# ProPrj_1300__2024-07-27.net
KiCad netlist of a schematic drawn in EasyEDA Pro
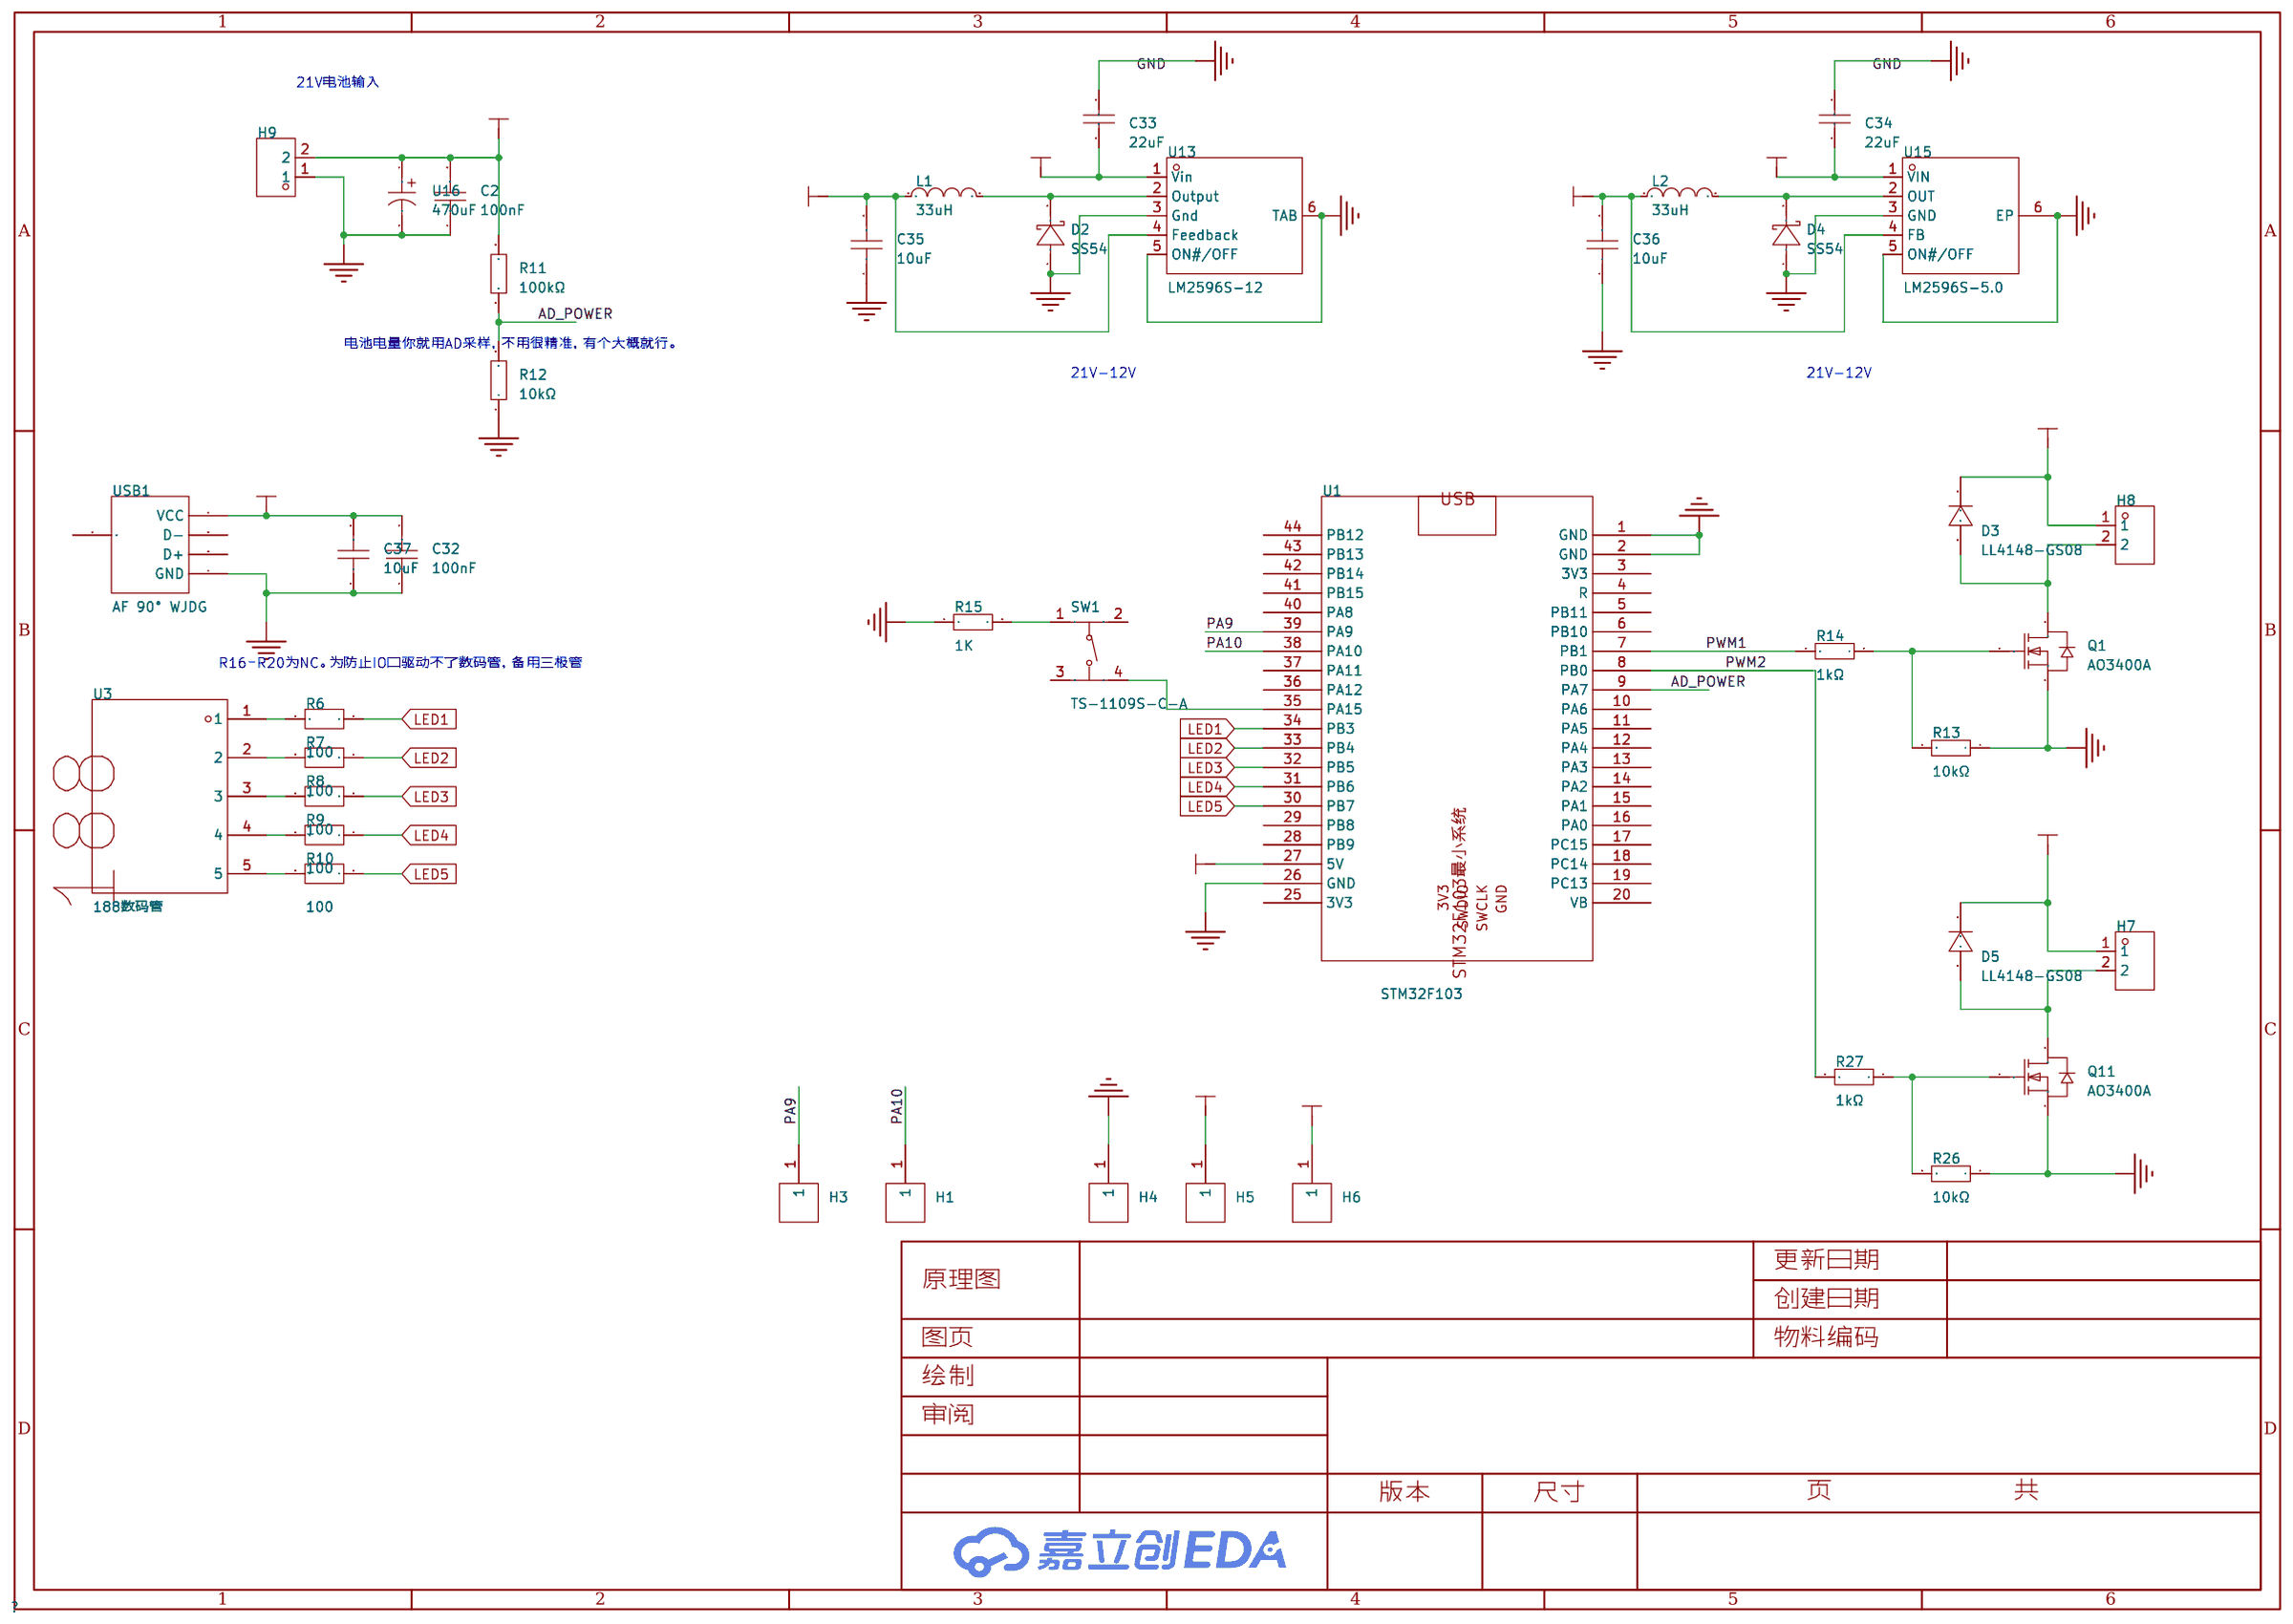
[diagram p0: schematic sheet]

(export (version "E")
  (design (tool "Eeschema 10.0.6"))
  (components
    (comp (ref "C2")
      (value "100nF")
      (footprint "easyedapro:C0603")
      (description "容值:100nF;精度:±10%;额定电压:50V;材质(温度系数):X7R;")
      (fields
        (field (name "Manufacturer Part") "CC0603KRX7R9BB104")
        (field (name "Manufacturer") "YAGEO(国巨)")
      )
      (libsource (lib "easyedapro") (part "CC0603KRX7R9BB104"))
    )
    (comp (ref "C32")
      (value "100nF")
      (footprint "easyedapro:C0603")
      (description "容值:100nF;精度:±10%;额定电压:50V;材质(温度系数):X7R;")
      (fields
        (field (name "Manufacturer Part") "CC0603KRX7R9BB104")
        (field (name "Manufacturer") "YAGEO(国巨)")
      )
      (libsource (lib "easyedapro") (part "CC0603KRX7R9BB104"))
    )
    (comp (ref "C33")
      (value "22uF")
      (footprint "easyedapro:C1206")
      (description "容值:22uF;精度:±10%;额定电压:25V;材质(温度系数):X5R;")
      (fields
        (field (name "Manufacturer Part") "CL31A226KAHNNNE")
        (field (name "Manufacturer") "SAMSUNG(三星)")
      )
      (libsource (lib "easyedapro") (part "CL31A226KAHNNNE"))
    )
    (comp (ref "C34")
      (value "22uF")
      (footprint "easyedapro:C1206")
      (description "容值:22uF;精度:±10%;额定电压:25V;材质(温度系数):X5R;")
      (fields
        (field (name "Manufacturer Part") "CL31A226KAHNNNE")
        (field (name "Manufacturer") "SAMSUNG(三星)")
      )
      (libsource (lib "easyedapro") (part "CL31A226KAHNNNE"))
    )
    (comp (ref "C35")
      (value "10uF")
      (footprint "easyedapro:C0805")
      (description "容值:10uF;精度:±10%;额定电压:25V;材质(温度系数):X5R;")
      (fields
        (field (name "Manufacturer Part") "CL21A106KAYNNNE")
        (field (name "Manufacturer") "SAMSUNG(三星)")
      )
      (libsource (lib "easyedapro") (part "CL21A106KAYNNNE"))
    )
    (comp (ref "C36")
      (value "10uF")
      (footprint "easyedapro:C0805")
      (description "容值:10uF;精度:±10%;额定电压:25V;材质(温度系数):X5R;")
      (fields
        (field (name "Manufacturer Part") "CL21A106KAYNNNE")
        (field (name "Manufacturer") "SAMSUNG(三星)")
      )
      (libsource (lib "easyedapro") (part "CL21A106KAYNNNE"))
    )
    (comp (ref "C37")
      (value "10uF")
      (footprint "easyedapro:C0805")
      (description "容值:10uF;精度:±10%;额定电压:25V;材质(温度系数):X5R;")
      (fields
        (field (name "Manufacturer Part") "CL21A106KAYNNNE")
        (field (name "Manufacturer") "SAMSUNG(三星)")
      )
      (libsource (lib "easyedapro") (part "CL21A106KAYNNNE"))
    )
    (comp (ref "D2")
      (value "SS54")
      (footprint "easyedapro:SMA_L4.3-W2.6-LS5.0-FD")
      (description "二极管配置:独立式;正向压降(Vf):550mV@5.0A;直流反向耐压(Vr):40V;平均整流电流(Io):5A;")
      (fields (field (name "Manufacturer") "宏迦橙"))
      (libsource (lib "easyedapro") (part "SS54_C7420369"))
    )
    (comp (ref "D3")
      (value "LL4148-GS08")
      (footprint "easyedapro:SOD-80_L3.5-W1.5-RD")
      (description "二极管配置:-;正向压降(Vf):860mV@50mA;直流反向耐压(Vr):75V;平均整流电流(Io):300mA;功率:500mW;反向恢复时间(trr):8ns;")
      (fields (field (name "Manufacturer") "VISHAY(威世)"))
      (libsource (lib "easyedapro") (part "LL4148-GS08"))
    )
    (comp (ref "D4")
      (value "SS54")
      (footprint "easyedapro:SMA_L4.3-W2.6-LS5.0-FD")
      (description "二极管配置:独立式;正向压降(Vf):550mV@5.0A;直流反向耐压(Vr):40V;平均整流电流(Io):5A;")
      (fields (field (name "Manufacturer") "宏迦橙"))
      (libsource (lib "easyedapro") (part "SS54_C7420369"))
    )
    (comp (ref "D5")
      (value "LL4148-GS08")
      (footprint "easyedapro:SOD-80_L3.5-W1.5-RD")
      (description "二极管配置:-;正向压降(Vf):860mV@50mA;直流反向耐压(Vr):75V;平均整流电流(Io):300mA;功率:500mW;反向恢复时间(trr):8ns;")
      (fields (field (name "Manufacturer") "VISHAY(威世)"))
      (libsource (lib "easyedapro") (part "LL4148-GS08"))
    )
    (comp (ref "H1")
      (value "PZ254V-11-01P")
      (footprint "easyedapro:HDR-TH_1P-P2.54-V-M")
      (fields (field (name "Manufacturer") "XFCN(兴飞)"))
      (libsource (lib "easyedapro") (part "PZ254V-11-01P"))
    )
    (comp (ref "H3")
      (value "PZ254V-11-01P")
      (footprint "easyedapro:HDR-TH_1P-P2.54-V-M")
      (fields (field (name "Manufacturer") "XFCN(兴飞)"))
      (libsource (lib "easyedapro") (part "PZ254V-11-01P"))
    )
    (comp (ref "H4")
      (value "PZ254V-11-01P")
      (footprint "easyedapro:HDR-TH_1P-P2.54-V-M")
      (fields (field (name "Manufacturer") "XFCN(兴飞)"))
      (libsource (lib "easyedapro") (part "PZ254V-11-01P"))
    )
    (comp (ref "H5")
      (value "PZ254V-11-01P")
      (footprint "easyedapro:HDR-TH_1P-P2.54-V-M")
      (fields (field (name "Manufacturer") "XFCN(兴飞)"))
      (libsource (lib "easyedapro") (part "PZ254V-11-01P"))
    )
    (comp (ref "H6")
      (value "PZ254V-11-01P")
      (footprint "easyedapro:HDR-TH_1P-P2.54-V-M")
      (fields (field (name "Manufacturer") "XFCN(兴飞)"))
      (libsource (lib "easyedapro") (part "PZ254V-11-01P"))
    )
    (comp (ref "H7")
      (value "PZ254V-11-02P")
      (footprint "easyedapro:HDR-TH_2P-P2.54-V-M")
      (fields (field (name "Manufacturer") "XFCN(兴飞)"))
      (libsource (lib "easyedapro") (part "PZ254V-11-02P"))
    )
    (comp (ref "H8")
      (value "PZ254V-11-02P")
      (footprint "easyedapro:HDR-TH_2P-P2.54-V-M")
      (fields (field (name "Manufacturer") "XFCN(兴飞)"))
      (libsource (lib "easyedapro") (part "PZ254V-11-02P"))
    )
    (comp (ref "H9")
      (value "PZ254V-11-02P")
      (footprint "easyedapro:HDR-TH_2P-P2.54-V-M")
      (fields (field (name "Manufacturer") "XFCN(兴飞)"))
      (libsource (lib "easyedapro") (part "PZ254V-11-02P"))
    )
    (comp (ref "L1")
      (value "33uH")
      (footprint "easyedapro:IND-SMD_L7.0-W6.6_FXL0630")
      (description "电感值:33uH;精度:±20%;额定电流:2A;饱和电流(Isat):2.5A;类型:一体成型电感;")
      (fields (field (name "Manufacturer Part") "FXL0630-330-M") (field (name "Manufacturer") "cjiang(长江微电)"))
      (libsource (lib "easyedapro") (part "FXL0630-330-M"))
    )
    (comp (ref "L2")
      (value "33uH")
      (footprint "easyedapro:IND-SMD_L7.0-W6.6_FXL0630")
      (description "电感值:33uH;精度:±20%;额定电流:2A;饱和电流(Isat):2.5A;类型:一体成型电感;")
      (fields (field (name "Manufacturer Part") "FXL0630-330-M") (field (name "Manufacturer") "cjiang(长江微电)"))
      (libsource (lib "easyedapro") (part "FXL0630-330-M"))
    )
    (comp (ref "Q1")
      (value "AO3400A")
      (footprint "easyedapro:SOT-23-3_L2.9-W1.6-P1.90-LS2.8-BR")
      (fields (field (name "Manufacturer") "AOS"))
      (libsource (lib "easyedapro") (part "AO3400A"))
    )
    (comp (ref "Q11")
      (value "AO3400A")
      (footprint "easyedapro:SOT-23-3_L2.9-W1.6-P1.90-LS2.8-BR")
      (fields (field (name "Manufacturer") "AOS"))
      (libsource (lib "easyedapro") (part "AO3400A"))
    )
    (comp (ref "R6") (value "100") (footprint "easyedapro:R0603") (libsource (lib "easyedapro") (part "100")))
    (comp (ref "R7") (value "100") (footprint "easyedapro:R0603") (libsource (lib "easyedapro") (part "100")))
    (comp (ref "R8") (value "100") (footprint "easyedapro:R0603") (libsource (lib "easyedapro") (part "100")))
    (comp (ref "R9") (value "100") (footprint "easyedapro:R0603") (libsource (lib "easyedapro") (part "100")))
    (comp (ref "R10")
      (value "100")
      (footprint "easyedapro:R0603")
      (libsource (lib "easyedapro") (part "100"))
    )
    (comp (ref "R11")
      (value "100kΩ")
      (footprint "easyedapro:R0603")
      (description "电阻类型:厚膜电阻;阻值:100kΩ;精度:±1%;功率:100mW;最大工作电压:75V;温度系数:±100ppm/°C;")
      (fields (field (name "Manufacturer Part") "RC0603FR-07100KL") (field (name "Manufacturer") "YAGEO(国巨)"))
      (libsource (lib "easyedapro") (part "RC0603FR-07100KL"))
    )
    (comp (ref "R12")
      (value "10kΩ")
      (footprint "easyedapro:R0603")
      (description "电阻类型:厚膜电阻;阻值:10kΩ;精度:±1%;功率:100mW;最大工作电压:75V;温度系数:±100ppm/°C;")
      (fields
        (field (name "Manufacturer Part") "0603WAF1002T5E")
        (field (name "Manufacturer") "UNI-ROYAL(厚声)")
      )
      (libsource (lib "easyedapro") (part "0603WAF1002T5E"))
    )
    (comp (ref "R13")
      (value "10kΩ")
      (footprint "easyedapro:R0603")
      (description "电阻类型:厚膜电阻;阻值:10kΩ;精度:±1%;功率:100mW;最大工作电压:75V;温度系数:±100ppm/°C;")
      (fields
        (field (name "Manufacturer Part") "0603WAF1002T5E")
        (field (name "Manufacturer") "UNI-ROYAL(厚声)")
      )
      (libsource (lib "easyedapro") (part "0603WAF1002T5E"))
    )
    (comp (ref "R14")
      (value "1kΩ")
      (footprint "easyedapro:R0603")
      (description "电阻类型:厚膜电阻;阻值:1kΩ;精度:±1%;功率:100mW;最大工作电压:75V;温度系数:±100ppm/°C;")
      (fields
        (field (name "Manufacturer Part") "0603WAF1001T5E")
        (field (name "Manufacturer") "UNI-ROYAL(厚声)")
      )
      (libsource (lib "easyedapro") (part "0603WAF1001T5E"))
    )
    (comp (ref "R15")
      (value "1K")
      (footprint "easyedapro:R0603")
      (description "电阻类型:厚膜电阻;阻值:10kΩ;精度:±1%;功率:100mW;最大工作电压:75V;温度系数:±100ppm/°C;")
      (fields
        (field (name "Manufacturer Part") "0603WAF1002T5E")
        (field (name "Manufacturer") "UNI-ROYAL(厚声)")
      )
      (libsource (lib "easyedapro") (part "0603WAF1002T5E"))
    )
    (comp (ref "R26")
      (value "10kΩ")
      (footprint "easyedapro:R0603")
      (description "电阻类型:厚膜电阻;阻值:10kΩ;精度:±1%;功率:100mW;最大工作电压:75V;温度系数:±100ppm/°C;")
      (fields
        (field (name "Manufacturer Part") "0603WAF1002T5E")
        (field (name "Manufacturer") "UNI-ROYAL(厚声)")
      )
      (libsource (lib "easyedapro") (part "0603WAF1002T5E"))
    )
    (comp (ref "R27")
      (value "1kΩ")
      (footprint "easyedapro:R0603")
      (description "电阻类型:厚膜电阻;阻值:1kΩ;精度:±1%;功率:100mW;最大工作电压:75V;温度系数:±100ppm/°C;")
      (fields
        (field (name "Manufacturer Part") "0603WAF1001T5E")
        (field (name "Manufacturer") "UNI-ROYAL(厚声)")
      )
      (libsource (lib "easyedapro") (part "0603WAF1001T5E"))
    )
    (comp (ref "SW1")
      (value "TS-1109S-C-A")
      (footprint "easyedapro:SW-SMD_4P-L4.5-W4.5-P3.00-LS7.0")
      (fields (field (name "Manufacturer") "XKB Connectivity(中国星坤)"))
      (libsource (lib "easyedapro") (part "TS-1109S-C-A"))
    )
    (comp (ref "U1")
      (value "STM32F103")
      (footprint "easyedapro:STM32FF103")
      (libsource (lib "easyedapro") (part "STM32F103"))
    )
    (comp (ref "U3") (value "188数码管") (libsource (lib "easyedapro") (part "188数码管")))
    (comp (ref "U13")
      (value "LM2596S-12")
      (footprint "easyedapro:TO-263-5_L10.0-W8.4-P1.70-LS15.3-BR")
      (description "功能类型:降压型;输出类型:固定;输入电压:40V;输出电压:12V;输出电流(最大值):3A;")
      (fields (field (name "Manufacturer") "UMW(友台半导体)"))
      (libsource (lib "easyedapro") (part "LM2596S-12"))
    )
    (comp (ref "U15")
      (value "LM2596S-5.0")
      (footprint "easyedapro:TO-263-5_L10.2-W8.9-P1.70-BR")
      (description "功能类型:降压型;输出类型:固定;输入电压:40V;输出电压:5V;输出电流(最大值):3A;")
      (fields (field (name "Manufacturer") "UMW(友台半导体)"))
      (libsource (lib "easyedapro") (part "LM2596S-5.0"))
    )
    (comp (ref "U16")
      (value "470uF")
      (footprint "easyedapro:CAP-TH_BD6.3-P2.50-D0.6-FD")
      (description "容值:470uF;精度:±20%;额定电压:25V;纹波电流:2.05A;等效串联电阻:35mΩ;")
      (fields (field (name "Manufacturer Part") "HT1E477M0611PC") (field (name "Manufacturer") "HONOR(荣誉)"))
      (libsource (lib "easyedapro") (part "HT1E477M0611PC"))
    )
    (comp (ref "USB1")
      (value "AF 90° WJDG")
      (footprint "easyedapro:USB-A-TH_AF-WJDG")
      (description "连接器类型:Type-A;标准:USB 2.0;公母:母;端口数量:1;触点数量:4P;安装方式:弯插;额定电流 - 电源:1.5A;工作温度范围:-25°C~+85°C;")
      (fields (field (name "Manufacturer") "SHOU HAN(首韩)"))
      (libsource (lib "easyedapro") (part "AF 90° WJDG"))
    )
  )
  (nets
    (net (code "1") (name "+5V") (class "Default")
      (node (ref "C32") (pin "2") (pinfunction "2_2") (pintype "unspecified"))
      (node (ref "C36") (pin "2") (pinfunction "2_2") (pintype "unspecified"))
      (node (ref "C37") (pin "2") (pinfunction "2_2") (pintype "unspecified"))
      (node (ref "H5") (pin "1") (pinfunction "1_1") (pintype "unspecified"))
      (node (ref "L2") (pin "1") (pinfunction "1_1") (pintype "unspecified"))
      (node (ref "U1") (pin "27") (pinfunction "5V_27") (pintype "unspecified"))
      (node (ref "U15") (pin "4") (pinfunction "FB_4") (pintype "unspecified"))
      (node (ref "USB1") (pin "1") (pinfunction "VCC_1") (pintype "input"))
    )
    (net (code "2") (name "/AD_POWER") (class "Default")
      (node (ref "R11") (pin "1") (pinfunction "1_1") (pintype "unspecified"))
      (node (ref "R12") (pin "2") (pinfunction "2_2") (pintype "input"))
      (node (ref "U1") (pin "9") (pinfunction "PA7_9") (pintype "unspecified"))
    )
    (net (code "3") (name "/PA9") (class "Default")
      (node (ref "H3") (pin "1") (pinfunction "1_1") (pintype "unspecified"))
      (node (ref "U1") (pin "39") (pinfunction "PA9_39") (pintype "unspecified"))
    )
    (net (code "4") (name "/PA10") (class "Default")
      (node (ref "H1") (pin "1") (pinfunction "1_1") (pintype "unspecified"))
      (node (ref "U1") (pin "38") (pinfunction "PA10_38") (pintype "unspecified"))
    )
    (net (code "5") (name "/PWM1") (class "Default")
      (node (ref "R14") (pin "2") (pinfunction "2_2") (pintype "input"))
      (node (ref "U1") (pin "7") (pinfunction "PB1_7") (pintype "unspecified"))
    )
    (net (code "6") (name "/PWM2") (class "Default")
      (node (ref "R27") (pin "2") (pinfunction "2_2") (pintype "input"))
      (node (ref "U1") (pin "8") (pinfunction "PB0_8") (pintype "unspecified"))
    )
    (net (code "7") (name "12V") (class "Default")
      (node (ref "C34") (pin "1") (pinfunction "1_1") (pintype "input"))
      (node (ref "C35") (pin "2") (pinfunction "2_2") (pintype "unspecified"))
      (node (ref "D3") (pin "1") (pinfunction "C_1") (pintype "unspecified"))
      (node (ref "D5") (pin "1") (pinfunction "C_1") (pintype "unspecified"))
      (node (ref "H6") (pin "1") (pinfunction "1_1") (pintype "unspecified"))
      (node (ref "H7") (pin "1") (pinfunction "1_1") (pintype "unspecified"))
      (node (ref "H8") (pin "1") (pinfunction "1_1") (pintype "unspecified"))
      (node (ref "L1") (pin "1") (pinfunction "1_1") (pintype "unspecified"))
      (node (ref "U13") (pin "4") (pinfunction "Feedback_4") (pintype "unspecified"))
      (node (ref "U15") (pin "1") (pinfunction "VIN_1") (pintype "unspecified"))
    )
    (net (code "8") (name "21V") (class "Default")
      (node (ref "C2") (pin "2") (pinfunction "2_2") (pintype "unspecified"))
      (node (ref "C33") (pin "1") (pinfunction "1_1") (pintype "input"))
      (node (ref "H9") (pin "2") (pinfunction "2_2") (pintype "unspecified"))
      (node (ref "R11") (pin "2") (pinfunction "2_2") (pintype "unspecified"))
      (node (ref "U13") (pin "1") (pinfunction "Vin_1") (pintype "unspecified"))
      (node (ref "U16") (pin "1") (pinfunction "1_1") (pintype "input"))
    )
    (net (code "9") (name "GND") (class "Default")
      (node (ref "C2") (pin "1") (pinfunction "1_1") (pintype "unspecified"))
      (node (ref "C32") (pin "1") (pinfunction "1_1") (pintype "unspecified"))
      (node (ref "C33") (pin "2") (pinfunction "2_2") (pintype "input"))
      (node (ref "C34") (pin "2") (pinfunction "2_2") (pintype "input"))
      (node (ref "C35") (pin "1") (pinfunction "1_1") (pintype "unspecified"))
      (node (ref "C36") (pin "1") (pinfunction "1_1") (pintype "unspecified"))
      (node (ref "C37") (pin "1") (pinfunction "1_1") (pintype "unspecified"))
      (node (ref "D2") (pin "1") (pinfunction "A_1") (pintype "unspecified"))
      (node (ref "D4") (pin "1") (pinfunction "A_1") (pintype "unspecified"))
      (node (ref "H4") (pin "1") (pinfunction "1_1") (pintype "unspecified"))
      (node (ref "H9") (pin "1") (pinfunction "1_1") (pintype "unspecified"))
      (node (ref "Q1") (pin "2") (pinfunction "S_2") (pintype "unspecified"))
      (node (ref "Q11") (pin "2") (pinfunction "S_2") (pintype "unspecified"))
      (node (ref "R12") (pin "1") (pinfunction "1_1") (pintype "input"))
      (node (ref "R13") (pin "1") (pinfunction "1_1") (pintype "input"))
      (node (ref "R15") (pin "1") (pinfunction "1_1") (pintype "input"))
      (node (ref "R26") (pin "1") (pinfunction "1_1") (pintype "input"))
      (node (ref "U1") (pin "1") (pinfunction "GND_1") (pintype "unspecified"))
      (node (ref "U1") (pin "2") (pinfunction "GND_2") (pintype "unspecified"))
      (node (ref "U1") (pin "26") (pinfunction "GND_26") (pintype "unspecified"))
      (node (ref "U13") (pin "3") (pinfunction "Gnd_3") (pintype "unspecified"))
      (node (ref "U13") (pin "5") (pinfunction "ON#/OFF_5") (pintype "unspecified"))
      (node (ref "U13") (pin "6") (pinfunction "TAB_6") (pintype "unspecified"))
      (node (ref "U15") (pin "3") (pinfunction "GND_3") (pintype "unspecified"))
      (node (ref "U15") (pin "5") (pinfunction "ON#/OFF_5") (pintype "unspecified"))
      (node (ref "U15") (pin "6") (pinfunction "EP_6") (pintype "unspecified"))
      (node (ref "U16") (pin "2") (pinfunction "2_2") (pintype "input"))
      (node (ref "USB1") (pin "4") (pinfunction "GND_4") (pintype "input"))
    )
    (net (code "10") (name "LED1") (class "Default")
      (node (ref "R6") (pin "1") (pinfunction "1_1") (pintype "unspecified"))
      (node (ref "U1") (pin "34") (pinfunction "PB3_34") (pintype "unspecified"))
    )
    (net (code "11") (name "LED2") (class "Default")
      (node (ref "R7") (pin "1") (pinfunction "1_1") (pintype "unspecified"))
      (node (ref "U1") (pin "33") (pinfunction "PB4_33") (pintype "unspecified"))
    )
    (net (code "12") (name "LED3") (class "Default")
      (node (ref "R8") (pin "1") (pinfunction "1_1") (pintype "unspecified"))
      (node (ref "U1") (pin "32") (pinfunction "PB5_32") (pintype "unspecified"))
    )
    (net (code "13") (name "LED4") (class "Default")
      (node (ref "R9") (pin "1") (pinfunction "1_1") (pintype "unspecified"))
      (node (ref "U1") (pin "31") (pinfunction "PB6_31") (pintype "unspecified"))
    )
    (net (code "14") (name "LED5") (class "Default")
      (node (ref "R10") (pin "1") (pinfunction "1_1") (pintype "unspecified"))
      (node (ref "U1") (pin "30") (pinfunction "PB7_30") (pintype "unspecified"))
    )
    (net (code "15") (name "Net-(D2-K)") (class "Default")
      (node (ref "D2") (pin "2") (pinfunction "K_2") (pintype "unspecified"))
      (node (ref "L1") (pin "2") (pinfunction "2_2") (pintype "unspecified"))
      (node (ref "U13") (pin "2") (pinfunction "Output_2") (pintype "unspecified"))
    )
    (net (code "16") (name "Net-(D3-A)") (class "Default")
      (node (ref "D3") (pin "2") (pinfunction "A_2") (pintype "unspecified"))
      (node (ref "H8") (pin "2") (pinfunction "2_2") (pintype "unspecified"))
      (node (ref "Q1") (pin "3") (pinfunction "D_3") (pintype "unspecified"))
    )
    (net (code "17") (name "Net-(D4-K)") (class "Default")
      (node (ref "D4") (pin "2") (pinfunction "K_2") (pintype "unspecified"))
      (node (ref "L2") (pin "2") (pinfunction "2_2") (pintype "unspecified"))
      (node (ref "U15") (pin "2") (pinfunction "OUT_2") (pintype "unspecified"))
    )
    (net (code "18") (name "Net-(D5-A)") (class "Default")
      (node (ref "D5") (pin "2") (pinfunction "A_2") (pintype "unspecified"))
      (node (ref "H7") (pin "2") (pinfunction "2_2") (pintype "unspecified"))
      (node (ref "Q11") (pin "3") (pinfunction "D_3") (pintype "unspecified"))
    )
    (net (code "19") (name "Net-(Q1-G)") (class "Default")
      (node (ref "Q1") (pin "1") (pinfunction "G_1") (pintype "unspecified"))
      (node (ref "R13") (pin "2") (pinfunction "2_2") (pintype "input"))
      (node (ref "R14") (pin "1") (pinfunction "1_1") (pintype "input"))
    )
    (net (code "20") (name "Net-(Q11-G)") (class "Default")
      (node (ref "Q11") (pin "1") (pinfunction "G_1") (pintype "unspecified"))
      (node (ref "R26") (pin "2") (pinfunction "2_2") (pintype "input"))
      (node (ref "R27") (pin "1") (pinfunction "1_1") (pintype "input"))
    )
    (net (code "21") (name "Net-(R6-Pad2)") (class "Default")
      (node (ref "R6") (pin "2") (pinfunction "2_2") (pintype "unspecified"))
      (node (ref "U3") (pin "1") (pinfunction "1_1") (pintype "unspecified"))
    )
    (net (code "22") (name "Net-(R7-Pad2)") (class "Default")
      (node (ref "R7") (pin "2") (pinfunction "2_2") (pintype "unspecified"))
      (node (ref "U3") (pin "2") (pinfunction "2_2") (pintype "unspecified"))
    )
    (net (code "23") (name "Net-(R8-Pad2)") (class "Default")
      (node (ref "R8") (pin "2") (pinfunction "2_2") (pintype "unspecified"))
      (node (ref "U3") (pin "3") (pinfunction "3_3") (pintype "unspecified"))
    )
    (net (code "24") (name "Net-(R9-Pad2)") (class "Default")
      (node (ref "R9") (pin "2") (pinfunction "2_2") (pintype "unspecified"))
      (node (ref "U3") (pin "4") (pinfunction "4_4") (pintype "unspecified"))
    )
    (net (code "25") (name "Net-(R10-Pad2)") (class "Default")
      (node (ref "R10") (pin "2") (pinfunction "2_2") (pintype "unspecified"))
      (node (ref "U3") (pin "5") (pinfunction "5_5") (pintype "unspecified"))
    )
    (net (code "26") (name "Net-(R15-Pad2)") (class "Default")
      (node (ref "R15") (pin "2") (pinfunction "2_2") (pintype "input"))
      (node (ref "SW1") (pin "1") (pinfunction "1_1") (pintype "unspecified"))
    )
    (net (code "27") (name "Net-(U1-PA15)") (class "Default")
      (node (ref "SW1") (pin "4") (pinfunction "4_4") (pintype "unspecified"))
      (node (ref "U1") (pin "35") (pinfunction "PA15_35") (pintype "unspecified"))
    )
    (net (code "28") (name "unconnected-(SW1-Pad2)") (class "Default")
      (node (ref "SW1") (pin "2") (pinfunction "2_2") (pintype "unspecified"))
    )
    (net (code "29") (name "unconnected-(SW1-Pad3)") (class "Default")
      (node (ref "SW1") (pin "3") (pinfunction "3_3") (pintype "unspecified"))
    )
    (net (code "30") (name "unconnected-(U1-3V3-Pad3)") (class "Default")
      (node (ref "U1") (pin "3") (pinfunction "3V3_3") (pintype "unspecified"))
    )
    (net (code "31") (name "unconnected-(U1-3V3-Pad25)") (class "Default")
      (node (ref "U1") (pin "25") (pinfunction "3V3_25") (pintype "unspecified"))
    )
    (net (code "32") (name "unconnected-(U1-PA0-Pad16)") (class "Default")
      (node (ref "U1") (pin "16") (pinfunction "PA0_16") (pintype "unspecified"))
    )
    (net (code "33") (name "unconnected-(U1-PA1-Pad15)") (class "Default")
      (node (ref "U1") (pin "15") (pinfunction "PA1_15") (pintype "unspecified"))
    )
    (net (code "34") (name "unconnected-(U1-PA2-Pad14)") (class "Default")
      (node (ref "U1") (pin "14") (pinfunction "PA2_14") (pintype "unspecified"))
    )
    (net (code "35") (name "unconnected-(U1-PA3-Pad13)") (class "Default")
      (node (ref "U1") (pin "13") (pinfunction "PA3_13") (pintype "unspecified"))
    )
    (net (code "36") (name "unconnected-(U1-PA4-Pad12)") (class "Default")
      (node (ref "U1") (pin "12") (pinfunction "PA4_12") (pintype "unspecified"))
    )
    (net (code "37") (name "unconnected-(U1-PA5-Pad11)") (class "Default")
      (node (ref "U1") (pin "11") (pinfunction "PA5_11") (pintype "unspecified"))
    )
    (net (code "38") (name "unconnected-(U1-PA6-Pad10)") (class "Default")
      (node (ref "U1") (pin "10") (pinfunction "PA6_10") (pintype "unspecified"))
    )
    (net (code "39") (name "unconnected-(U1-PA8-Pad40)") (class "Default")
      (node (ref "U1") (pin "40") (pinfunction "PA8_40") (pintype "unspecified"))
    )
    (net (code "40") (name "unconnected-(U1-PA11-Pad37)") (class "Default")
      (node (ref "U1") (pin "37") (pinfunction "PA11_37") (pintype "unspecified"))
    )
    (net (code "41") (name "unconnected-(U1-PA12-Pad36)") (class "Default")
      (node (ref "U1") (pin "36") (pinfunction "PA12_36") (pintype "unspecified"))
    )
    (net (code "42") (name "unconnected-(U1-PB8-Pad29)") (class "Default")
      (node (ref "U1") (pin "29") (pinfunction "PB8_29") (pintype "unspecified"))
    )
    (net (code "43") (name "unconnected-(U1-PB9-Pad28)") (class "Default")
      (node (ref "U1") (pin "28") (pinfunction "PB9_28") (pintype "unspecified"))
    )
    (net (code "44") (name "unconnected-(U1-PB10-Pad6)") (class "Default")
      (node (ref "U1") (pin "6") (pinfunction "PB10_6") (pintype "unspecified"))
    )
    (net (code "45") (name "unconnected-(U1-PB11-Pad5)") (class "Default")
      (node (ref "U1") (pin "5") (pinfunction "PB11_5") (pintype "unspecified"))
    )
    (net (code "46") (name "unconnected-(U1-PB12-Pad44)") (class "Default")
      (node (ref "U1") (pin "44") (pinfunction "PB12_44") (pintype "unspecified"))
    )
    (net (code "47") (name "unconnected-(U1-PB13-Pad43)") (class "Default")
      (node (ref "U1") (pin "43") (pinfunction "PB13_43") (pintype "unspecified"))
    )
    (net (code "48") (name "unconnected-(U1-PB14-Pad42)") (class "Default")
      (node (ref "U1") (pin "42") (pinfunction "PB14_42") (pintype "unspecified"))
    )
    (net (code "49") (name "unconnected-(U1-PB15-Pad41)") (class "Default")
      (node (ref "U1") (pin "41") (pinfunction "PB15_41") (pintype "unspecified"))
    )
    (net (code "50") (name "unconnected-(U1-PC13-Pad19)") (class "Default")
      (node (ref "U1") (pin "19") (pinfunction "PC13_19") (pintype "unspecified"))
    )
    (net (code "51") (name "unconnected-(U1-PC14-Pad18)") (class "Default")
      (node (ref "U1") (pin "18") (pinfunction "PC14_18") (pintype "unspecified"))
    )
    (net (code "52") (name "unconnected-(U1-PC15-Pad17)") (class "Default")
      (node (ref "U1") (pin "17") (pinfunction "PC15_17") (pintype "unspecified"))
    )
    (net (code "53") (name "unconnected-(U1-R-Pad4)") (class "Default")
      (node (ref "U1") (pin "4") (pinfunction "R_4") (pintype "unspecified"))
    )
    (net (code "54") (name "unconnected-(U1-VB-Pad20)") (class "Default")
      (node (ref "U1") (pin "20") (pinfunction "VB_20") (pintype "unspecified"))
    )
    (net (code "55") (name "unconnected-(USB1-D+-Pad3)") (class "Default")
      (node (ref "USB1") (pin "3") (pinfunction "D+_3") (pintype "input"))
    )
    (net (code "56") (name "unconnected-(USB1-D--Pad2)") (class "Default")
      (node (ref "USB1") (pin "2") (pinfunction "D-_2") (pintype "input"))
    )
    (net (code "57") (name "unconnected-(USB1-SHLD-Pad5)") (class "Default")
      (node (ref "USB1") (pin "5") (pinfunction "SHLD_5") (pintype "unspecified"))
    )
  )
)
